# L_R_OSMC.net
KiCad netlist of a schematic drawn in EAGLE
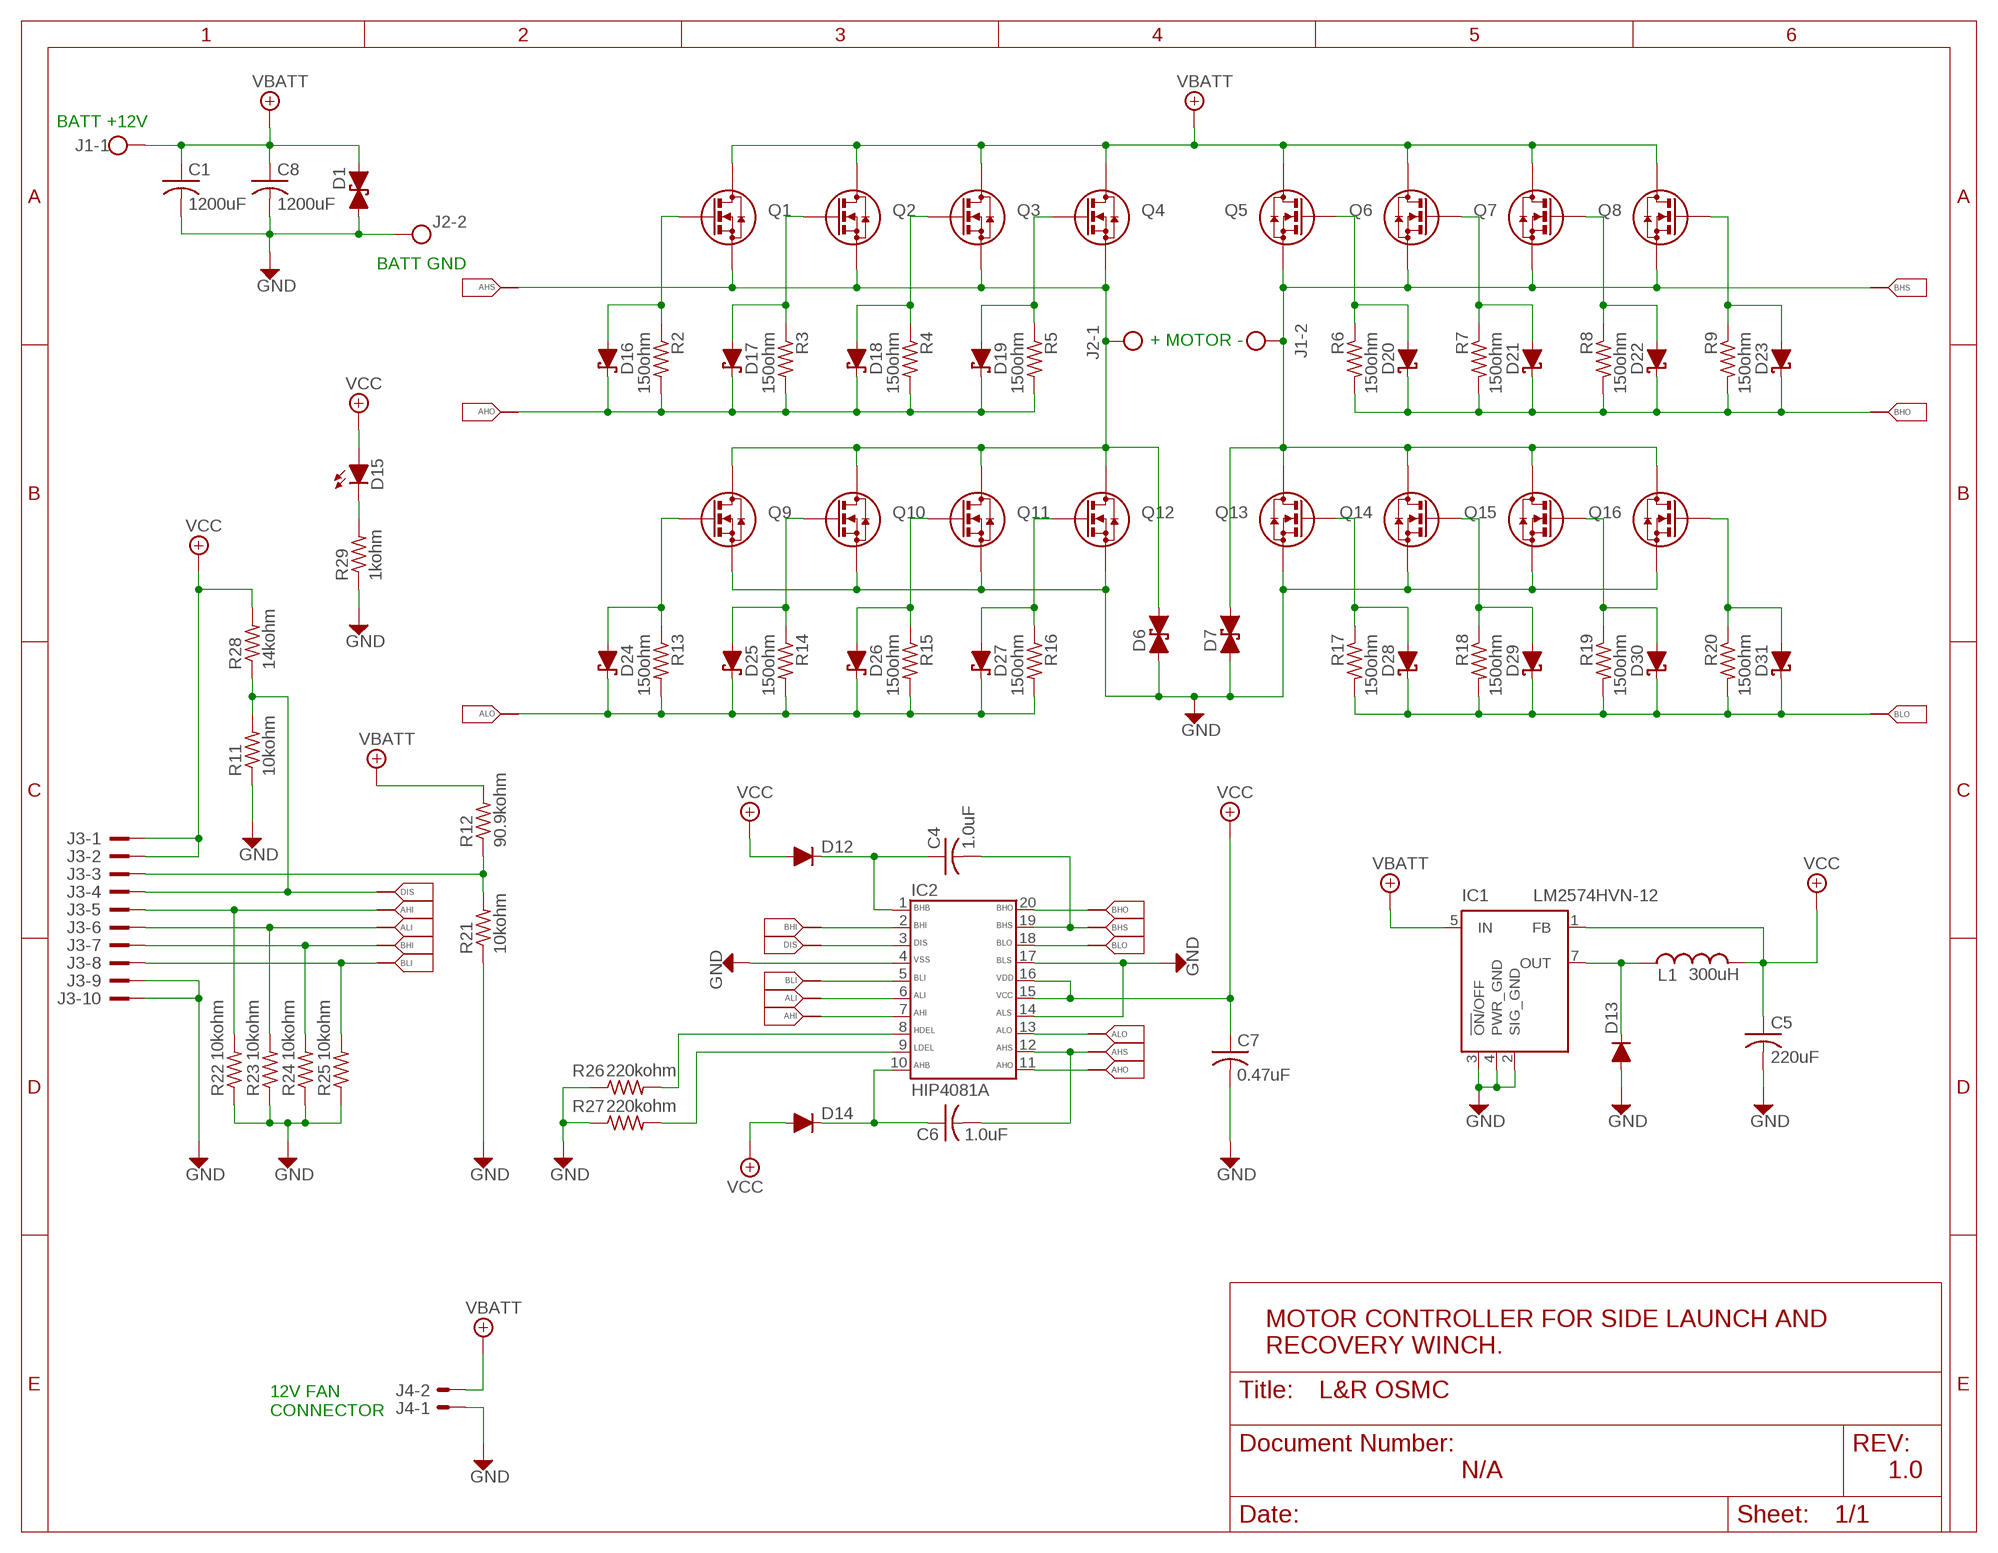
[diagram p0: schematic, sheet 1]

(export (version "E")
  (design (tool "Eeschema 10.0.6"))
  (components
    (comp (ref "C1")
      (value "1200uF")
      (footprint "eagle-import:E7,5-18")
      (fields (field (name "MF") "Panasonic") (field (name "MPN") "EEU-FC1J681S"))
      (libsource (lib "eagle-import") (part "C1,8"))
    )
    (comp (ref "C4")
      (value "1.0uF")
      (footprint "eagle-import:C050-075X075")
      (fields (field (name "MF") "Panasonic") (field (name "MPN") "ECQ-V1H105JL"))
      (libsource (lib "eagle-import") (part "C4,6"))
    )
    (comp (ref "C5")
      (value "220uF")
      (footprint "eagle-import:E5-6")
      (fields (field (name "MF") "Panasonic") (field (name "MPN") "ECA-1CM221"))
      (libsource (lib "eagle-import") (part "C5"))
    )
    (comp (ref "C6")
      (value "1.0uF")
      (footprint "eagle-import:C050-075X075")
      (fields (field (name "MF") "Panasonic") (field (name "MPN") "ECQ-V1H105JL"))
      (libsource (lib "eagle-import") (part "C4,6"))
    )
    (comp (ref "C7")
      (value "0.47uF")
      (footprint "eagle-import:C050-025X075")
      (fields (field (name "MF") "TDK Corporation") (field (name "MPN") "FK28X5R1C474K"))
      (libsource (lib "eagle-import") (part "C7"))
    )
    (comp (ref "C8")
      (value "1200uF")
      (footprint "eagle-import:E7,5-18")
      (fields (field (name "MF") "Panasonic") (field (name "MPN") "EEU-FC1J681S"))
      (libsource (lib "eagle-import") (part "C1,8"))
    )
    (comp (ref "D1")
      (value "1.5KE51CA")
      (footprint "eagle-import:1.5KE")
      (fields (field (name "MF") "Vishay") (field (name "MPN") "1.5KE51CA-E3/54"))
      (libsource (lib "eagle-import") (part "1.5KE51CA"))
    )
    (comp (ref "D6")
      (value "1.5KE51CA")
      (footprint "eagle-import:1.5KE")
      (fields (field (name "MF") "Vishay") (field (name "MPN") "1.5KE51CA-E3/54"))
      (libsource (lib "eagle-import") (part "1.5KE51CA"))
    )
    (comp (ref "D7")
      (value "1.5KE51CA")
      (footprint "eagle-import:1.5KE")
      (fields (field (name "MF") "Vishay") (field (name "MPN") "1.5KE51CA-E3/54"))
      (libsource (lib "eagle-import") (part "1.5KE51CA"))
    )
    (comp (ref "D12")
      (value "UF1002")
      (footprint "eagle-import:DO41")
      (fields (field (name "MF") "Diodes Inc.") (field (name "MPN") "UF1002-T"))
      (libsource (lib "eagle-import") (part "UF1002"))
    )
    (comp (ref "D13")
      (value "UF1002")
      (footprint "eagle-import:DO41")
      (fields (field (name "MF") "Diodes Inc.") (field (name "MPN") "UF1002-T"))
      (libsource (lib "eagle-import") (part "UF1002"))
    )
    (comp (ref "D14")
      (value "UF1002")
      (footprint "eagle-import:DO41")
      (fields (field (name "MF") "Diodes Inc.") (field (name "MPN") "UF1002-T"))
      (libsource (lib "eagle-import") (part "UF1002"))
    )
    (comp (ref "D15")
      (value "LED")
      (footprint "eagle-import:LED5MM")
      (libsource (lib "eagle-import") (part "LED"))
    )
    (comp (ref "D16")
      (value "1N6263")
      (footprint "eagle-import:DO35-7")
      (libsource (lib "eagle-import") (part "1N6263"))
    )
    (comp (ref "D17")
      (value "1N6263")
      (footprint "eagle-import:DO35-7")
      (libsource (lib "eagle-import") (part "1N6263"))
    )
    (comp (ref "D18")
      (value "1N6263")
      (footprint "eagle-import:DO35-7")
      (libsource (lib "eagle-import") (part "1N6263"))
    )
    (comp (ref "D19")
      (value "1N6263")
      (footprint "eagle-import:DO35-7")
      (libsource (lib "eagle-import") (part "1N6263"))
    )
    (comp (ref "D20")
      (value "1N6263")
      (footprint "eagle-import:DO35-7")
      (libsource (lib "eagle-import") (part "1N6263"))
    )
    (comp (ref "D21")
      (value "1N6263")
      (footprint "eagle-import:DO35-7")
      (libsource (lib "eagle-import") (part "1N6263"))
    )
    (comp (ref "D22")
      (value "1N6263")
      (footprint "eagle-import:DO35-7")
      (libsource (lib "eagle-import") (part "1N6263"))
    )
    (comp (ref "D23")
      (value "1N6263")
      (footprint "eagle-import:DO35-7")
      (libsource (lib "eagle-import") (part "1N6263"))
    )
    (comp (ref "D24")
      (value "1N6263")
      (footprint "eagle-import:DO35-7")
      (libsource (lib "eagle-import") (part "1N6263"))
    )
    (comp (ref "D25")
      (value "1N6263")
      (footprint "eagle-import:DO35-7")
      (libsource (lib "eagle-import") (part "1N6263"))
    )
    (comp (ref "D26")
      (value "1N6263")
      (footprint "eagle-import:DO35-7")
      (libsource (lib "eagle-import") (part "1N6263"))
    )
    (comp (ref "D27")
      (value "1N6263")
      (footprint "eagle-import:DO35-7")
      (libsource (lib "eagle-import") (part "1N6263"))
    )
    (comp (ref "D28")
      (value "1N6263")
      (footprint "eagle-import:DO35-7")
      (libsource (lib "eagle-import") (part "1N6263"))
    )
    (comp (ref "D29")
      (value "1N6263")
      (footprint "eagle-import:DO35-7")
      (libsource (lib "eagle-import") (part "1N6263"))
    )
    (comp (ref "D30")
      (value "1N6263")
      (footprint "eagle-import:DO35-7")
      (libsource (lib "eagle-import") (part "1N6263"))
    )
    (comp (ref "D31")
      (value "1N6263")
      (footprint "eagle-import:DO35-7")
      (libsource (lib "eagle-import") (part "1N6263"))
    )
    (comp (ref "IC1")
      (value "LM2574HVN-12")
      (footprint "eagle-import:DIL08")
      (libsource (lib "eagle-import") (part "LM2574?-HVN12"))
    )
    (comp (ref "IC2")
      (value "HIP4081A")
      (footprint "eagle-import:DIL20")
      (fields (field (name "MF") "Intersil") (field (name "MPN") "HIP4081AIPZ"))
      (libsource (lib "eagle-import") (part "HIP4081A"))
    )
    (comp (ref "J1")
      (value "LXXX-2")
      (footprint "eagle-import:LXXX-2")
      (fields (field (name "MF") "Weidmuller") (field (name "MPN") "1047290000"))
      (libsource (lib "eagle-import") (part "LXXX-2"))
    )
    (comp (ref "J2")
      (value "LXXX-2")
      (footprint "eagle-import:LXXX-2")
      (fields (field (name "MF") "Weidmuller") (field (name "MPN") "1047290000"))
      (libsource (lib "eagle-import") (part "LXXX-2"))
    )
    (comp (ref "J3")
      (value "3793")
      (footprint "eagle-import:3M_3793-10")
      (fields (field (name "MF") "3M") (field (name "MPN") "3793-6002"))
      (libsource (lib "eagle-import") (part "3793"))
    )
    (comp (ref "J4")
      (value "22-23-2021")
      (footprint "eagle-import:22-23-2021")
      (fields (field (name "MF") "MOLEX"))
      (libsource (lib "eagle-import") (part "22-23-2021"))
    )
    (comp (ref "L1")
      (value "300uH")
      (footprint "eagle-import:L06X18")
      (fields (field (name "MF") "API Delevan") (field (name "MPN") "2474R-31L"))
      (libsource (lib "eagle-import") (part "L1"))
    )
    (comp (ref "Q1")
      (value "IRF14051-16")
      (footprint "eagle-import:TO-220AB")
      (fields (field (name "MF") "International Rectifier") (field (name "MPN") "IRF1405PBF"))
      (libsource (lib "eagle-import") (part "IRF14051-16"))
    )
    (comp (ref "Q2")
      (value "IRF14051-16")
      (footprint "eagle-import:TO-220AB")
      (fields (field (name "MF") "International Rectifier") (field (name "MPN") "IRF1405PBF"))
      (libsource (lib "eagle-import") (part "IRF14051-16"))
    )
    (comp (ref "Q3")
      (value "IRF14051-16")
      (footprint "eagle-import:TO-220AB")
      (fields (field (name "MF") "International Rectifier") (field (name "MPN") "IRF1405PBF"))
      (libsource (lib "eagle-import") (part "IRF14051-16"))
    )
    (comp (ref "Q4")
      (value "IRF14051-16")
      (footprint "eagle-import:TO-220AB")
      (fields (field (name "MF") "International Rectifier") (field (name "MPN") "IRF1405PBF"))
      (libsource (lib "eagle-import") (part "IRF14051-16"))
    )
    (comp (ref "Q5")
      (value "IRF14051-16")
      (footprint "eagle-import:TO-220AB")
      (fields (field (name "MF") "International Rectifier") (field (name "MPN") "IRF1405PBF"))
      (libsource (lib "eagle-import") (part "IRF14051-16"))
    )
    (comp (ref "Q6")
      (value "IRF14051-16")
      (footprint "eagle-import:TO-220AB")
      (fields (field (name "MF") "International Rectifier") (field (name "MPN") "IRF1405PBF"))
      (libsource (lib "eagle-import") (part "IRF14051-16"))
    )
    (comp (ref "Q7")
      (value "IRF14051-16")
      (footprint "eagle-import:TO-220AB")
      (fields (field (name "MF") "International Rectifier") (field (name "MPN") "IRF1405PBF"))
      (libsource (lib "eagle-import") (part "IRF14051-16"))
    )
    (comp (ref "Q8")
      (value "IRF14051-16")
      (footprint "eagle-import:TO-220AB")
      (fields (field (name "MF") "International Rectifier") (field (name "MPN") "IRF1405PBF"))
      (libsource (lib "eagle-import") (part "IRF14051-16"))
    )
    (comp (ref "Q9")
      (value "IRF14051-16")
      (footprint "eagle-import:TO-220AB")
      (fields (field (name "MF") "International Rectifier") (field (name "MPN") "IRF1405PBF"))
      (libsource (lib "eagle-import") (part "IRF14051-16"))
    )
    (comp (ref "Q10")
      (value "IRF14051-16")
      (footprint "eagle-import:TO-220AB")
      (fields (field (name "MF") "International Rectifier") (field (name "MPN") "IRF1405PBF"))
      (libsource (lib "eagle-import") (part "IRF14051-16"))
    )
    (comp (ref "Q11")
      (value "IRF14051-16")
      (footprint "eagle-import:TO-220AB")
      (fields (field (name "MF") "International Rectifier") (field (name "MPN") "IRF1405PBF"))
      (libsource (lib "eagle-import") (part "IRF14051-16"))
    )
    (comp (ref "Q12")
      (value "IRF14051-16")
      (footprint "eagle-import:TO-220AB")
      (fields (field (name "MF") "International Rectifier") (field (name "MPN") "IRF1405PBF"))
      (libsource (lib "eagle-import") (part "IRF14051-16"))
    )
    (comp (ref "Q13")
      (value "IRF14051-16")
      (footprint "eagle-import:TO-220AB")
      (fields (field (name "MF") "International Rectifier") (field (name "MPN") "IRF1405PBF"))
      (libsource (lib "eagle-import") (part "IRF14051-16"))
    )
    (comp (ref "Q14")
      (value "IRF14051-16")
      (footprint "eagle-import:TO-220AB")
      (fields (field (name "MF") "International Rectifier") (field (name "MPN") "IRF1405PBF"))
      (libsource (lib "eagle-import") (part "IRF14051-16"))
    )
    (comp (ref "Q15")
      (value "IRF14051-16")
      (footprint "eagle-import:TO-220AB")
      (fields (field (name "MF") "International Rectifier") (field (name "MPN") "IRF1405PBF"))
      (libsource (lib "eagle-import") (part "IRF14051-16"))
    )
    (comp (ref "Q16")
      (value "IRF14051-16")
      (footprint "eagle-import:TO-220AB")
      (fields (field (name "MF") "International Rectifier") (field (name "MPN") "IRF1405PBF"))
      (libsource (lib "eagle-import") (part "IRF14051-16"))
    )
    (comp (ref "R2")
      (value "150ohm")
      (footprint "eagle-import:0207_7")
      (libsource (lib "eagle-import") (part "R"))
    )
    (comp (ref "R3")
      (value "150ohm")
      (footprint "eagle-import:0207_7")
      (libsource (lib "eagle-import") (part "R"))
    )
    (comp (ref "R4")
      (value "150ohm")
      (footprint "eagle-import:0207_7")
      (libsource (lib "eagle-import") (part "R"))
    )
    (comp (ref "R5")
      (value "150ohm")
      (footprint "eagle-import:0207_7")
      (libsource (lib "eagle-import") (part "R"))
    )
    (comp (ref "R6")
      (value "150ohm")
      (footprint "eagle-import:0207_7")
      (libsource (lib "eagle-import") (part "R"))
    )
    (comp (ref "R7")
      (value "150ohm")
      (footprint "eagle-import:0207_7")
      (libsource (lib "eagle-import") (part "R"))
    )
    (comp (ref "R8")
      (value "150ohm")
      (footprint "eagle-import:0207_7")
      (libsource (lib "eagle-import") (part "R"))
    )
    (comp (ref "R9")
      (value "150ohm")
      (footprint "eagle-import:0207_7")
      (libsource (lib "eagle-import") (part "R"))
    )
    (comp (ref "R11")
      (value "10kohm")
      (footprint "eagle-import:0207_7")
      (libsource (lib "eagle-import") (part "R"))
    )
    (comp (ref "R12")
      (value "90.9kohm")
      (footprint "eagle-import:0207_7")
      (libsource (lib "eagle-import") (part "R"))
    )
    (comp (ref "R13")
      (value "150ohm")
      (footprint "eagle-import:0207_7")
      (libsource (lib "eagle-import") (part "R"))
    )
    (comp (ref "R14")
      (value "150ohm")
      (footprint "eagle-import:0207_7")
      (libsource (lib "eagle-import") (part "R"))
    )
    (comp (ref "R15")
      (value "150ohm")
      (footprint "eagle-import:0207_7")
      (libsource (lib "eagle-import") (part "R"))
    )
    (comp (ref "R16")
      (value "150ohm")
      (footprint "eagle-import:0207_7")
      (libsource (lib "eagle-import") (part "R"))
    )
    (comp (ref "R17")
      (value "150ohm")
      (footprint "eagle-import:0207_7")
      (libsource (lib "eagle-import") (part "R"))
    )
    (comp (ref "R18")
      (value "150ohm")
      (footprint "eagle-import:0207_7")
      (libsource (lib "eagle-import") (part "R"))
    )
    (comp (ref "R19")
      (value "150ohm")
      (footprint "eagle-import:0207_7")
      (libsource (lib "eagle-import") (part "R"))
    )
    (comp (ref "R20")
      (value "150ohm")
      (footprint "eagle-import:0207_7")
      (libsource (lib "eagle-import") (part "R"))
    )
    (comp (ref "R21")
      (value "10kohm")
      (footprint "eagle-import:0207_7")
      (libsource (lib "eagle-import") (part "R"))
    )
    (comp (ref "R22")
      (value "10kohm")
      (footprint "eagle-import:0207_7")
      (libsource (lib "eagle-import") (part "R"))
    )
    (comp (ref "R23")
      (value "10kohm")
      (footprint "eagle-import:0207_7")
      (libsource (lib "eagle-import") (part "R"))
    )
    (comp (ref "R24")
      (value "10kohm")
      (footprint "eagle-import:0207_7")
      (libsource (lib "eagle-import") (part "R"))
    )
    (comp (ref "R25")
      (value "10kohm")
      (footprint "eagle-import:0207_7")
      (libsource (lib "eagle-import") (part "R"))
    )
    (comp (ref "R26")
      (value "220kohm")
      (footprint "eagle-import:0207_7")
      (libsource (lib "eagle-import") (part "R"))
    )
    (comp (ref "R27")
      (value "220kohm")
      (footprint "eagle-import:0207_7")
      (libsource (lib "eagle-import") (part "R"))
    )
    (comp (ref "R28")
      (value "14kohm")
      (footprint "eagle-import:0207_7")
      (libsource (lib "eagle-import") (part "R"))
    )
    (comp (ref "R29")
      (value "1kohm")
      (footprint "eagle-import:0207_7")
      (libsource (lib "eagle-import") (part "R"))
    )
  )
  (nets
    (net (code "1") (name "/AHI") (class "Default")
      (node (ref "IC2") (pin "7") (pinfunction "7_7") (pintype "passive"))
      (node (ref "J3") (pin "P$5") (pinfunction "KL_P$5") (pintype "passive"))
      (node (ref "R22") (pin "2") (pinfunction "2_2") (pintype "passive"))
    )
    (net (code "2") (name "/AHO") (class "Default")
      (node (ref "D16") (pin "C") (pinfunction "C_C") (pintype "passive"))
      (node (ref "D17") (pin "C") (pinfunction "C_C") (pintype "passive"))
      (node (ref "D18") (pin "C") (pinfunction "C_C") (pintype "passive"))
      (node (ref "D19") (pin "C") (pinfunction "C_C") (pintype "passive"))
      (node (ref "IC2") (pin "11") (pinfunction "11_11") (pintype "passive"))
      (node (ref "R2") (pin "2") (pinfunction "2_2") (pintype "passive"))
      (node (ref "R3") (pin "2") (pinfunction "2_2") (pintype "passive"))
      (node (ref "R4") (pin "2") (pinfunction "2_2") (pintype "passive"))
      (node (ref "R5") (pin "2") (pinfunction "2_2") (pintype "passive"))
    )
    (net (code "3") (name "/AHS") (class "Default")
      (node (ref "C6") (pin "2") (pinfunction "2_2") (pintype "passive"))
      (node (ref "D6") (pin "C") (pinfunction "2_C") (pintype "passive"))
      (node (ref "IC2") (pin "12") (pinfunction "12_12") (pintype "passive"))
      (node (ref "J2") (pin "P$1") (pinfunction "KL_P$1") (pintype "passive"))
      (node (ref "J2") (pin "P$2") (pinfunction "KL_P$2") (pintype "passive"))
      (node (ref "J2") (pin "P$3") (pinfunction "KL_P$3") (pintype "passive"))
      (node (ref "J2") (pin "P$4") (pinfunction "KL_P$4") (pintype "passive"))
      (node (ref "Q1") (pin "D") (pinfunction "D_D") (pintype "passive"))
      (node (ref "Q10") (pin "S") (pinfunction "S_S") (pintype "passive"))
      (node (ref "Q11") (pin "S") (pinfunction "S_S") (pintype "passive"))
      (node (ref "Q12") (pin "S") (pinfunction "S_S") (pintype "passive"))
      (node (ref "Q2") (pin "D") (pinfunction "D_D") (pintype "passive"))
      (node (ref "Q3") (pin "D") (pinfunction "D_D") (pintype "passive"))
      (node (ref "Q4") (pin "D") (pinfunction "D_D") (pintype "passive"))
      (node (ref "Q9") (pin "S") (pinfunction "S_S") (pintype "passive"))
    )
    (net (code "4") (name "/ALI") (class "Default")
      (node (ref "IC2") (pin "6") (pinfunction "6_6") (pintype "passive"))
      (node (ref "J3") (pin "P$6") (pinfunction "KL_P$6") (pintype "passive"))
      (node (ref "R23") (pin "2") (pinfunction "2_2") (pintype "passive"))
    )
    (net (code "5") (name "/ALO") (class "Default")
      (node (ref "D24") (pin "C") (pinfunction "C_C") (pintype "passive"))
      (node (ref "D25") (pin "C") (pinfunction "C_C") (pintype "passive"))
      (node (ref "D26") (pin "C") (pinfunction "C_C") (pintype "passive"))
      (node (ref "D27") (pin "C") (pinfunction "C_C") (pintype "passive"))
      (node (ref "IC2") (pin "13") (pinfunction "13_13") (pintype "passive"))
      (node (ref "R13") (pin "2") (pinfunction "2_2") (pintype "passive"))
      (node (ref "R14") (pin "2") (pinfunction "2_2") (pintype "passive"))
      (node (ref "R15") (pin "2") (pinfunction "2_2") (pintype "passive"))
      (node (ref "R16") (pin "2") (pinfunction "2_2") (pintype "passive"))
    )
    (net (code "6") (name "/BHI") (class "Default")
      (node (ref "IC2") (pin "2") (pinfunction "2_2") (pintype "passive"))
      (node (ref "J3") (pin "P$7") (pinfunction "KL_P$7") (pintype "passive"))
      (node (ref "R24") (pin "2") (pinfunction "2_2") (pintype "passive"))
    )
    (net (code "7") (name "/BHO") (class "Default")
      (node (ref "D20") (pin "C") (pinfunction "C_C") (pintype "passive"))
      (node (ref "D21") (pin "C") (pinfunction "C_C") (pintype "passive"))
      (node (ref "D22") (pin "C") (pinfunction "C_C") (pintype "passive"))
      (node (ref "D23") (pin "C") (pinfunction "C_C") (pintype "passive"))
      (node (ref "IC2") (pin "20") (pinfunction "20_20") (pintype "passive"))
      (node (ref "R6") (pin "2") (pinfunction "2_2") (pintype "passive"))
      (node (ref "R7") (pin "2") (pinfunction "2_2") (pintype "passive"))
      (node (ref "R8") (pin "2") (pinfunction "2_2") (pintype "passive"))
      (node (ref "R9") (pin "2") (pinfunction "2_2") (pintype "passive"))
    )
    (net (code "8") (name "/BHS") (class "Default")
      (node (ref "C4") (pin "2") (pinfunction "2_2") (pintype "passive"))
      (node (ref "D7") (pin "C") (pinfunction "2_C") (pintype "passive"))
      (node (ref "IC2") (pin "19") (pinfunction "19_19") (pintype "passive"))
      (node (ref "J1") (pin "P$5") (pinfunction "KL_P$5") (pintype "passive"))
      (node (ref "J1") (pin "P$6") (pinfunction "KL_P$6") (pintype "passive"))
      (node (ref "J1") (pin "P$7") (pinfunction "KL_P$7") (pintype "passive"))
      (node (ref "J1") (pin "P$8") (pinfunction "KL_P$8") (pintype "passive"))
      (node (ref "Q13") (pin "S") (pinfunction "S_S") (pintype "passive"))
      (node (ref "Q14") (pin "S") (pinfunction "S_S") (pintype "passive"))
      (node (ref "Q15") (pin "S") (pinfunction "S_S") (pintype "passive"))
      (node (ref "Q16") (pin "S") (pinfunction "S_S") (pintype "passive"))
      (node (ref "Q5") (pin "D") (pinfunction "D_D") (pintype "passive"))
      (node (ref "Q6") (pin "D") (pinfunction "D_D") (pintype "passive"))
      (node (ref "Q7") (pin "D") (pinfunction "D_D") (pintype "passive"))
      (node (ref "Q8") (pin "D") (pinfunction "D_D") (pintype "passive"))
    )
    (net (code "9") (name "/BLI") (class "Default")
      (node (ref "IC2") (pin "5") (pinfunction "5_5") (pintype "passive"))
      (node (ref "J3") (pin "P$8") (pinfunction "KL_P$8") (pintype "passive"))
      (node (ref "R25") (pin "2") (pinfunction "2_2") (pintype "passive"))
    )
    (net (code "10") (name "/BLO") (class "Default")
      (node (ref "D28") (pin "C") (pinfunction "C_C") (pintype "passive"))
      (node (ref "D29") (pin "C") (pinfunction "C_C") (pintype "passive"))
      (node (ref "D30") (pin "C") (pinfunction "C_C") (pintype "passive"))
      (node (ref "D31") (pin "C") (pinfunction "C_C") (pintype "passive"))
      (node (ref "IC2") (pin "18") (pinfunction "18_18") (pintype "passive"))
      (node (ref "R17") (pin "2") (pinfunction "2_2") (pintype "passive"))
      (node (ref "R18") (pin "2") (pinfunction "2_2") (pintype "passive"))
      (node (ref "R19") (pin "2") (pinfunction "2_2") (pintype "passive"))
      (node (ref "R20") (pin "2") (pinfunction "2_2") (pintype "passive"))
    )
    (net (code "11") (name "/DIS") (class "Default")
      (node (ref "IC2") (pin "3") (pinfunction "3_3") (pintype "passive"))
      (node (ref "J3") (pin "P$4") (pinfunction "KL_P$4") (pintype "passive"))
      (node (ref "R11") (pin "2") (pinfunction "2_2") (pintype "passive"))
      (node (ref "R28") (pin "1") (pinfunction "1_1") (pintype "passive"))
    )
    (net (code "12") (name "GND") (class "Default")
      (node (ref "C1") (pin "-") (pinfunction "2_-") (pintype "passive"))
      (node (ref "C5") (pin "-") (pinfunction "2_-") (pintype "passive"))
      (node (ref "C7") (pin "2") (pinfunction "2_2") (pintype "passive"))
      (node (ref "C8") (pin "-") (pinfunction "2_-") (pintype "passive"))
      (node (ref "D1") (pin "A") (pinfunction "1_A") (pintype "passive"))
      (node (ref "D13") (pin "A") (pinfunction "A_A") (pintype "passive"))
      (node (ref "D6") (pin "A") (pinfunction "1_A") (pintype "passive"))
      (node (ref "D7") (pin "A") (pinfunction "1_A") (pintype "passive"))
      (node (ref "IC1") (pin "2") (pinfunction "SIG_GND_2") (pintype "input"))
      (node (ref "IC1") (pin "3") (pinfunction "~{ON}/OFF_3") (pintype "input"))
      (node (ref "IC1") (pin "4") (pinfunction "PWR_GND_4") (pintype "power_in"))
      (node (ref "IC2") (pin "14") (pinfunction "14_14") (pintype "passive"))
      (node (ref "IC2") (pin "17") (pinfunction "17_17") (pintype "passive"))
      (node (ref "IC2") (pin "4") (pinfunction "4_4") (pintype "passive"))
      (node (ref "J2") (pin "P$5") (pinfunction "KL_P$5") (pintype "passive"))
      (node (ref "J2") (pin "P$6") (pinfunction "KL_P$6") (pintype "passive"))
      (node (ref "J2") (pin "P$7") (pinfunction "KL_P$7") (pintype "passive"))
      (node (ref "J2") (pin "P$8") (pinfunction "KL_P$8") (pintype "passive"))
      (node (ref "J3") (pin "P$10") (pinfunction "KL_P$10") (pintype "passive"))
      (node (ref "J3") (pin "P$9") (pinfunction "KL_P$9") (pintype "passive"))
      (node (ref "J4") (pin "1") (pinfunction "S_1") (pintype "passive"))
      (node (ref "Q10") (pin "D") (pinfunction "D_D") (pintype "passive"))
      (node (ref "Q11") (pin "D") (pinfunction "D_D") (pintype "passive"))
      (node (ref "Q12") (pin "D") (pinfunction "D_D") (pintype "passive"))
      (node (ref "Q13") (pin "D") (pinfunction "D_D") (pintype "passive"))
      (node (ref "Q14") (pin "D") (pinfunction "D_D") (pintype "passive"))
      (node (ref "Q15") (pin "D") (pinfunction "D_D") (pintype "passive"))
      (node (ref "Q16") (pin "D") (pinfunction "D_D") (pintype "passive"))
      (node (ref "Q9") (pin "D") (pinfunction "D_D") (pintype "passive"))
      (node (ref "R11") (pin "1") (pinfunction "1_1") (pintype "passive"))
      (node (ref "R21") (pin "1") (pinfunction "1_1") (pintype "passive"))
      (node (ref "R22") (pin "1") (pinfunction "1_1") (pintype "passive"))
      (node (ref "R23") (pin "1") (pinfunction "1_1") (pintype "passive"))
      (node (ref "R24") (pin "1") (pinfunction "1_1") (pintype "passive"))
      (node (ref "R25") (pin "1") (pinfunction "1_1") (pintype "passive"))
      (node (ref "R26") (pin "1") (pinfunction "1_1") (pintype "passive"))
      (node (ref "R27") (pin "1") (pinfunction "1_1") (pintype "passive"))
      (node (ref "R29") (pin "1") (pinfunction "1_1") (pintype "passive"))
    )
    (net (code "13") (name "Net-(C4-Pad1)") (class "Default")
      (node (ref "C4") (pin "1") (pinfunction "1_1") (pintype "passive"))
      (node (ref "D12") (pin "C") (pinfunction "C_C") (pintype "passive"))
      (node (ref "IC2") (pin "1") (pinfunction "1_1") (pintype "passive"))
    )
    (net (code "14") (name "Net-(C6-Pad1)") (class "Default")
      (node (ref "C6") (pin "1") (pinfunction "1_1") (pintype "passive"))
      (node (ref "D14") (pin "C") (pinfunction "C_C") (pintype "passive"))
      (node (ref "IC2") (pin "10") (pinfunction "10_10") (pintype "passive"))
    )
    (net (code "15") (name "Net-(D15-C)") (class "Default")
      (node (ref "D15") (pin "K") (pinfunction "C_K") (pintype "passive"))
      (node (ref "R29") (pin "2") (pinfunction "2_2") (pintype "passive"))
    )
    (net (code "16") (name "Net-(D16-PadA)") (class "Default")
      (node (ref "D16") (pin "A") (pinfunction "A_A") (pintype "passive"))
      (node (ref "Q1") (pin "G") (pinfunction "G_G") (pintype "passive"))
      (node (ref "R2") (pin "1") (pinfunction "1_1") (pintype "passive"))
    )
    (net (code "17") (name "Net-(D17-PadA)") (class "Default")
      (node (ref "D17") (pin "A") (pinfunction "A_A") (pintype "passive"))
      (node (ref "Q2") (pin "G") (pinfunction "G_G") (pintype "passive"))
      (node (ref "R3") (pin "1") (pinfunction "1_1") (pintype "passive"))
    )
    (net (code "18") (name "Net-(D18-PadA)") (class "Default")
      (node (ref "D18") (pin "A") (pinfunction "A_A") (pintype "passive"))
      (node (ref "Q3") (pin "G") (pinfunction "G_G") (pintype "passive"))
      (node (ref "R4") (pin "1") (pinfunction "1_1") (pintype "passive"))
    )
    (net (code "19") (name "Net-(D19-PadA)") (class "Default")
      (node (ref "D19") (pin "A") (pinfunction "A_A") (pintype "passive"))
      (node (ref "Q4") (pin "G") (pinfunction "G_G") (pintype "passive"))
      (node (ref "R5") (pin "1") (pinfunction "1_1") (pintype "passive"))
    )
    (net (code "20") (name "Net-(D20-PadA)") (class "Default")
      (node (ref "D20") (pin "A") (pinfunction "A_A") (pintype "passive"))
      (node (ref "Q5") (pin "G") (pinfunction "G_G") (pintype "passive"))
      (node (ref "R6") (pin "1") (pinfunction "1_1") (pintype "passive"))
    )
    (net (code "21") (name "Net-(D21-PadA)") (class "Default")
      (node (ref "D21") (pin "A") (pinfunction "A_A") (pintype "passive"))
      (node (ref "Q6") (pin "G") (pinfunction "G_G") (pintype "passive"))
      (node (ref "R7") (pin "1") (pinfunction "1_1") (pintype "passive"))
    )
    (net (code "22") (name "Net-(D22-PadA)") (class "Default")
      (node (ref "D22") (pin "A") (pinfunction "A_A") (pintype "passive"))
      (node (ref "Q7") (pin "G") (pinfunction "G_G") (pintype "passive"))
      (node (ref "R8") (pin "1") (pinfunction "1_1") (pintype "passive"))
    )
    (net (code "23") (name "Net-(D23-PadA)") (class "Default")
      (node (ref "D23") (pin "A") (pinfunction "A_A") (pintype "passive"))
      (node (ref "Q8") (pin "G") (pinfunction "G_G") (pintype "passive"))
      (node (ref "R9") (pin "1") (pinfunction "1_1") (pintype "passive"))
    )
    (net (code "24") (name "Net-(D24-PadA)") (class "Default")
      (node (ref "D24") (pin "A") (pinfunction "A_A") (pintype "passive"))
      (node (ref "Q9") (pin "G") (pinfunction "G_G") (pintype "passive"))
      (node (ref "R13") (pin "1") (pinfunction "1_1") (pintype "passive"))
    )
    (net (code "25") (name "Net-(D25-PadA)") (class "Default")
      (node (ref "D25") (pin "A") (pinfunction "A_A") (pintype "passive"))
      (node (ref "Q10") (pin "G") (pinfunction "G_G") (pintype "passive"))
      (node (ref "R14") (pin "1") (pinfunction "1_1") (pintype "passive"))
    )
    (net (code "26") (name "Net-(D26-PadA)") (class "Default")
      (node (ref "D26") (pin "A") (pinfunction "A_A") (pintype "passive"))
      (node (ref "Q11") (pin "G") (pinfunction "G_G") (pintype "passive"))
      (node (ref "R15") (pin "1") (pinfunction "1_1") (pintype "passive"))
    )
    (net (code "27") (name "Net-(D27-PadA)") (class "Default")
      (node (ref "D27") (pin "A") (pinfunction "A_A") (pintype "passive"))
      (node (ref "Q12") (pin "G") (pinfunction "G_G") (pintype "passive"))
      (node (ref "R16") (pin "1") (pinfunction "1_1") (pintype "passive"))
    )
    (net (code "28") (name "Net-(D28-PadA)") (class "Default")
      (node (ref "D28") (pin "A") (pinfunction "A_A") (pintype "passive"))
      (node (ref "Q13") (pin "G") (pinfunction "G_G") (pintype "passive"))
      (node (ref "R17") (pin "1") (pinfunction "1_1") (pintype "passive"))
    )
    (net (code "29") (name "Net-(D29-PadA)") (class "Default")
      (node (ref "D29") (pin "A") (pinfunction "A_A") (pintype "passive"))
      (node (ref "Q14") (pin "G") (pinfunction "G_G") (pintype "passive"))
      (node (ref "R18") (pin "1") (pinfunction "1_1") (pintype "passive"))
    )
    (net (code "30") (name "Net-(D30-PadA)") (class "Default")
      (node (ref "D30") (pin "A") (pinfunction "A_A") (pintype "passive"))
      (node (ref "Q15") (pin "G") (pinfunction "G_G") (pintype "passive"))
      (node (ref "R19") (pin "1") (pinfunction "1_1") (pintype "passive"))
    )
    (net (code "31") (name "Net-(D31-PadA)") (class "Default")
      (node (ref "D31") (pin "A") (pinfunction "A_A") (pintype "passive"))
      (node (ref "Q16") (pin "G") (pinfunction "G_G") (pintype "passive"))
      (node (ref "R20") (pin "1") (pinfunction "1_1") (pintype "passive"))
    )
    (net (code "32") (name "Net-(IC1-OUT)") (class "Default")
      (node (ref "D13") (pin "C") (pinfunction "C_C") (pintype "passive"))
      (node (ref "IC1") (pin "7") (pinfunction "OUT_7") (pintype "passive"))
      (node (ref "L1") (pin "1") (pinfunction "1_1") (pintype "passive"))
    )
    (net (code "33") (name "Net-(IC2-Pad8)") (class "Default")
      (node (ref "IC2") (pin "8") (pinfunction "8_8") (pintype "passive"))
      (node (ref "R26") (pin "2") (pinfunction "2_2") (pintype "passive"))
    )
    (net (code "34") (name "Net-(IC2-Pad9)") (class "Default")
      (node (ref "IC2") (pin "9") (pinfunction "9_9") (pintype "passive"))
      (node (ref "R27") (pin "2") (pinfunction "2_2") (pintype "passive"))
    )
    (net (code "35") (name "Net-(J3D-KL)") (class "Default")
      (node (ref "J3") (pin "P$3") (pinfunction "KL_P$3") (pintype "passive"))
      (node (ref "R12") (pin "1") (pinfunction "1_1") (pintype "passive"))
      (node (ref "R21") (pin "2") (pinfunction "2_2") (pintype "passive"))
    )
    (net (code "36") (name "VBATT") (class "Default")
      (node (ref "C1") (pin "+") (pinfunction "1_+") (pintype "passive"))
      (node (ref "C8") (pin "+") (pinfunction "1_+") (pintype "passive"))
      (node (ref "D1") (pin "C") (pinfunction "2_C") (pintype "passive"))
      (node (ref "IC1") (pin "5") (pinfunction "IN_5") (pintype "input"))
      (node (ref "J1") (pin "P$1") (pinfunction "KL_P$1") (pintype "passive"))
      (node (ref "J1") (pin "P$2") (pinfunction "KL_P$2") (pintype "passive"))
      (node (ref "J1") (pin "P$3") (pinfunction "KL_P$3") (pintype "passive"))
      (node (ref "J1") (pin "P$4") (pinfunction "KL_P$4") (pintype "passive"))
      (node (ref "J4") (pin "2") (pinfunction "S_2") (pintype "passive"))
      (node (ref "Q1") (pin "S") (pinfunction "S_S") (pintype "passive"))
      (node (ref "Q2") (pin "S") (pinfunction "S_S") (pintype "passive"))
      (node (ref "Q3") (pin "S") (pinfunction "S_S") (pintype "passive"))
      (node (ref "Q4") (pin "S") (pinfunction "S_S") (pintype "passive"))
      (node (ref "Q5") (pin "S") (pinfunction "S_S") (pintype "passive"))
      (node (ref "Q6") (pin "S") (pinfunction "S_S") (pintype "passive"))
      (node (ref "Q7") (pin "S") (pinfunction "S_S") (pintype "passive"))
      (node (ref "Q8") (pin "S") (pinfunction "S_S") (pintype "passive"))
      (node (ref "R12") (pin "2") (pinfunction "2_2") (pintype "passive"))
    )
    (net (code "37") (name "VCC") (class "Default")
      (node (ref "C5") (pin "+") (pinfunction "1_+") (pintype "passive"))
      (node (ref "C7") (pin "1") (pinfunction "1_1") (pintype "passive"))
      (node (ref "D12") (pin "A") (pinfunction "A_A") (pintype "passive"))
      (node (ref "D14") (pin "A") (pinfunction "A_A") (pintype "passive"))
      (node (ref "D15") (pin "A") (pinfunction "A_A") (pintype "passive"))
      (node (ref "IC1") (pin "1") (pinfunction "FB_1") (pintype "input"))
      (node (ref "IC2") (pin "15") (pinfunction "15_15") (pintype "passive"))
      (node (ref "IC2") (pin "16") (pinfunction "16_16") (pintype "passive"))
      (node (ref "J3") (pin "P$1") (pinfunction "KL_P$1") (pintype "passive"))
      (node (ref "J3") (pin "P$2") (pinfunction "KL_P$2") (pintype "passive"))
      (node (ref "L1") (pin "2") (pinfunction "2_2") (pintype "passive"))
      (node (ref "R28") (pin "2") (pinfunction "2_2") (pintype "passive"))
    )
  )
)
